# 5V_and_3V3_Outputs.net
KiCad netlist of a schematic drawn in Altium Designer
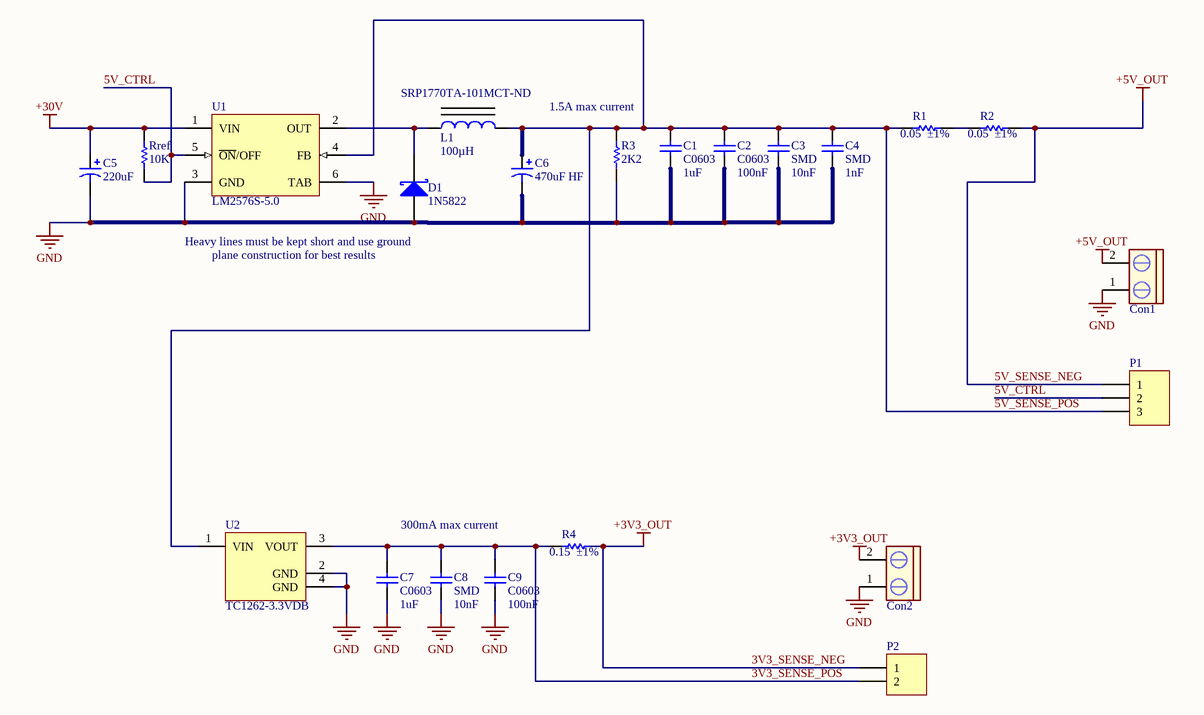
[diagram p0: 5V and 3V3 Outputs.SchDoc]

(export (version "E")
  (design (tool "Eeschema 10.0.6"))
  (components
    (comp (ref "C1")
      (value "C0603")
      (footprint "0603")
      (description "C1608X7R1C105K X7R")
      (fields (field (name "ALTIUM_VALUE") "1uF") (field (name "PUBLISHER") "Altium Limited"))
      (libsource (lib "KEMET Chip Capacitor") (part "C0603"))
    )
    (comp (ref "C2")
      (value "C0603")
      (footprint "0603")
      (description "C1608X7R1C105K X7R")
      (fields (field (name "ALTIUM_VALUE") "100nF") (field (name "PUBLISHER") "Altium Limited"))
      (libsource (lib "KEMET Chip Capacitor") (part "C0603"))
    )
    (comp (ref "C3")
      (value "SMD")
      (footprint "1206")
      (description "Ceramic Chip Capacitor - Standard")
      (fields (field (name "ALTIUM_VALUE") "10nF") (field (name "PUBLISHER") "Altium Limited"))
      (libsource (lib "KEMET Chip Capacitor") (part "C1206"))
    )
    (comp (ref "C4")
      (value "SMD")
      (footprint "1206")
      (description "Ceramic Chip Capacitor - Standard")
      (fields (field (name "ALTIUM_VALUE") "1nF") (field (name "PUBLISHER") "Altium Limited"))
      (libsource (lib "KEMET Chip Capacitor") (part "C1206"))
    )
    (comp (ref "C5")
      (value "220uF")
      (footprint "CAPPR5-10X16")
      (description "Aluminum Electrolytic Capacitor, Radial Style with Long Leads: 220uF, 63V")
      (fields (field (name "PUBLISHER") "Altium Limited"))
      (libsource (lib "Vishay Roederstein Electrolytic Radial-Lead Capacitor") (part "EKA00DD322J00"))
    )
    (comp (ref "C6")
      (value "470uF HF")
      (footprint "CAPPR5-10X20")
      (description "Aluminum Electrolytic Capacitor, Radial Style with Long Leads: 470uF, 25V")
      (fields (field (name "PUBLISHER") "Altium Limited"))
      (libsource (lib "Vishay Roederstein Electrolytic Radial-Lead Capacitor") (part "EKC00DE347E00"))
    )
    (comp (ref "C7")
      (value "C0603")
      (footprint "0603")
      (description "C1608X7R1C105K X7R")
      (fields (field (name "ALTIUM_VALUE") "1uF") (field (name "PUBLISHER") "Altium Limited"))
      (libsource (lib "KEMET Chip Capacitor") (part "C0603"))
    )
    (comp (ref "C8")
      (value "SMD")
      (footprint "1206")
      (description "Ceramic Chip Capacitor - Standard")
      (fields (field (name "ALTIUM_VALUE") "10nF") (field (name "PUBLISHER") "Altium Limited"))
      (libsource (lib "KEMET Chip Capacitor") (part "C1206"))
    )
    (comp (ref "C9")
      (value "C0603")
      (footprint "0603")
      (description "C1608X7R1C105K X7R")
      (fields (field (name "ALTIUM_VALUE") "100nF") (field (name "PUBLISHER") "Altium Limited"))
      (libsource (lib "KEMET Chip Capacitor") (part "C0603"))
    )
    (comp (ref "Con1")
      (value "Salida Buck")
      (footprint "My_CN2")
      (description "Connector blue screw")
      (libsource (lib "Mylib") (part "CON2 pin blue"))
    )
    (comp (ref "Con2")
      (value "Salida Buck")
      (footprint "My_CN2")
      (description "Connector blue screw")
      (libsource (lib "Mylib") (part "CON2 pin blue"))
    )
    (comp (ref "D1")
      (value "1N5822")
      (footprint "Vertical DO-201AD 10.5mm")
      (description "Generic Schottky Diode")
      (libsource (lib "NXT - Diodes") (part "Generic Schottky Diode"))
    )
    (comp (ref "L1")
      (value "Ferrite Inductor")
      (footprint "SRP1770TA Series")
      (fields
        (field (name "MANUFACTURER PART NUMBER") "SRP1770TA-101M")
        (field (name "TOLERANCE") "±20%")
        (field (name "SUPPLIER PART NUMBER") "SRP1770TA-101MCT-ND")
        (field (name "MANUFACTURER") "Bourns Inc.")
        (field (name "INDUCTANCE") "100µH")
      )
      (libsource (lib "NXT - Inductors") (part "Ferrite Inductor"))
    )
    (comp (ref "P1")
      (value "Header 3")
      (footprint "My_1X03")
      (description "Header, 3-Pin")
      (fields (field (name "PUBLISHER") "Altium Limited"))
      (libsource (lib "Mylib") (part "Header 3"))
    )
    (comp (ref "P2")
      (value "Header 2")
      (footprint "My_1X02")
      (description "Header, 2-Pin")
      (fields (field (name "PUBLISHER") "Altium Limited"))
      (libsource (lib "Mylib") (part "Header 2"))
    )
    (comp (ref "R1")
      (value "ERJL1W")
      (footprint "L1W-2512")
      (fields
        (field (name "MANUFACTURER PART NUMBER") "PE2512FKE070R05L")
        (field (name "MANUFACTURER") "Yageo")
        (field (name "RESISTANCE (OHMS)") "0.05")
        (field (name "TOLERANCE") "±1%")
        (field (name "PUBLISHER") "Altium Limited")
      )
      (libsource (lib "Panasonic Resistor") (part "ERJL1W"))
    )
    (comp (ref "R2")
      (value "ERJL1W")
      (footprint "L1W-2512")
      (fields
        (field (name "MANUFACTURER PART NUMBER") "PE2512FKE070R05L")
        (field (name "MANUFACTURER") "Yageo")
        (field (name "RESISTANCE (OHMS)") "0.05")
        (field (name "TOLERANCE") "±1%")
        (field (name "PUBLISHER") "Altium Limited")
      )
      (libsource (lib "Panasonic Resistor") (part "ERJL1W"))
    )
    (comp (ref "R3")
      (value "2K2")
      (footprint "ERA-0603")
      (fields (field (name "PUBLISHER") "Altium Limited"))
      (libsource (lib "Panasonic Resistor") (part "ERA3Y"))
    )
    (comp (ref "R4")
      (value "SMD")
      (footprint "8RB-1206")
      (fields
        (field (name "RESISTANCE (OHMS)") "0.15")
        (field (name "MANUFACTURER PART NUMBER") "KRL1632E-M-R150-F-T5")
        (field (name "TOLERANCE") "±1%")
        (field (name "MANUFACTURER") "Susumu")
      )
      (libsource (lib "Panasonic Resistor") (part "ERJ8BQ"))
    )
    (comp (ref "Rref")
      (value "10K")
      (footprint "ERA-0603")
      (fields (field (name "PUBLISHER") "Altium Limited"))
      (libsource (lib "Panasonic Resistor") (part "ERA3Y"))
    )
    (comp (ref "U1")
      (value "LM2576S-5.0")
      (footprint "TS5B_N")
      (description "SIMPLE SWITCHER® 3A Step-Down Voltage Regulator, 5-pin TO-263")
      (fields (field (name "MANUFACTURER") "National Semiconductor"))
      (libsource (lib "National Semiconductor Switcher") (part "LM2576S-5.0"))
    )
    (comp (ref "U2")
      (value "TC1262-3.3VDB")
      (footprint "SOT-223-DB3_N")
      (description "500mA Fixed Output CMOS LDO, 3-Pin SOT-223, Extended Temperature")
      (fields (field (name "MANUFACTURER") "Microchip"))
      (libsource (lib "Microchip Power Management Line Regulator") (part "TC1262-3.3VDB"))
    )
  )
  (nets
    (net (code "1") (name "+3V3_OUT") (class "Default")
      (node (ref "Con2") (pin "2") (pinfunction "2_2") (pintype "passive"))
      (node (ref "P2") (pin "1") (pinfunction "1_1") (pintype "passive"))
      (node (ref "R4") (pin "2") (pinfunction "2_2") (pintype "passive"))
    )
    (net (code "2") (name "+5V_OUT") (class "Default")
      (node (ref "Con1") (pin "2") (pinfunction "2_2") (pintype "passive"))
      (node (ref "P1") (pin "1") (pinfunction "1_1") (pintype "passive"))
      (node (ref "R2") (pin "2") (pinfunction "2_2") (pintype "passive"))
    )
    (net (code "3") (name "+30V") (class "Default")
      (node (ref "C5") (pin "1") (pinfunction "1_1") (pintype "passive"))
      (node (ref "Rref") (pin "2") (pinfunction "2_2") (pintype "passive"))
      (node (ref "U1") (pin "1") (pinfunction "VIN_1") (pintype "power_in"))
    )
    (net (code "4") (name "/3V3_SENSE_POS") (class "Default")
      (node (ref "C7") (pin "2") (pinfunction "2_2") (pintype "passive"))
      (node (ref "C8") (pin "2") (pinfunction "2_2") (pintype "passive"))
      (node (ref "C9") (pin "2") (pinfunction "2_2") (pintype "passive"))
      (node (ref "P2") (pin "2") (pinfunction "2_2") (pintype "passive"))
      (node (ref "R4") (pin "1") (pinfunction "1_1") (pintype "passive"))
      (node (ref "U2") (pin "3") (pinfunction "VOUT_3") (pintype "power_in"))
    )
    (net (code "5") (name "/5V_CTRL") (class "Default")
      (node (ref "P1") (pin "2") (pinfunction "2_2") (pintype "passive"))
      (node (ref "Rref") (pin "1") (pinfunction "1_1") (pintype "passive"))
      (node (ref "U1") (pin "5") (pinfunction "~{ON}/OFF_5") (pintype "input"))
    )
    (net (code "6") (name "/5V_SENSE_POS") (class "Default")
      (node (ref "C1") (pin "2") (pinfunction "2_2") (pintype "passive"))
      (node (ref "C2") (pin "2") (pinfunction "2_2") (pintype "passive"))
      (node (ref "C3") (pin "2") (pinfunction "2_2") (pintype "passive"))
      (node (ref "C4") (pin "2") (pinfunction "2_2") (pintype "passive"))
      (node (ref "C6") (pin "1") (pinfunction "1_1") (pintype "passive"))
      (node (ref "L1") (pin "2") (pinfunction "2_2") (pintype "passive"))
      (node (ref "P1") (pin "3") (pinfunction "3_3") (pintype "passive"))
      (node (ref "R1") (pin "1") (pinfunction "1_1") (pintype "passive"))
      (node (ref "R3") (pin "2") (pinfunction "2_2") (pintype "passive"))
      (node (ref "U1") (pin "4") (pinfunction "FB_4") (pintype "input"))
      (node (ref "U2") (pin "1") (pinfunction "VIN_1") (pintype "power_in"))
    )
    (net (code "7") (name "GND") (class "Default")
      (node (ref "C1") (pin "1") (pinfunction "1_1") (pintype "passive"))
      (node (ref "C2") (pin "1") (pinfunction "1_1") (pintype "passive"))
      (node (ref "C3") (pin "1") (pinfunction "1_1") (pintype "passive"))
      (node (ref "C4") (pin "1") (pinfunction "1_1") (pintype "passive"))
      (node (ref "C5") (pin "2") (pinfunction "2_2") (pintype "passive"))
      (node (ref "C6") (pin "2") (pinfunction "2_2") (pintype "passive"))
      (node (ref "C7") (pin "1") (pinfunction "1_1") (pintype "passive"))
      (node (ref "C8") (pin "1") (pinfunction "1_1") (pintype "passive"))
      (node (ref "C9") (pin "1") (pinfunction "1_1") (pintype "passive"))
      (node (ref "Con1") (pin "1") (pinfunction "1_1") (pintype "passive"))
      (node (ref "Con2") (pin "1") (pinfunction "1_1") (pintype "passive"))
      (node (ref "D1") (pin "1") (pinfunction "A_1") (pintype "passive"))
      (node (ref "R3") (pin "1") (pinfunction "1_1") (pintype "passive"))
      (node (ref "U1") (pin "3") (pinfunction "GND_3") (pintype "power_in"))
      (node (ref "U1") (pin "6") (pinfunction "TAB_6") (pintype "power_in"))
      (node (ref "U2") (pin "2") (pinfunction "GND_2") (pintype "power_in"))
      (node (ref "U2") (pin "4") (pinfunction "GND_4") (pintype "power_in"))
    )
    (net (code "8") (name "Net-(D1-K)") (class "Default")
      (node (ref "D1") (pin "2") (pinfunction "K_2") (pintype "passive"))
      (node (ref "L1") (pin "1") (pinfunction "1_1") (pintype "passive"))
      (node (ref "U1") (pin "2") (pinfunction "OUT_2") (pintype "power_in"))
    )
    (net (code "9") (name "Net-(R1-Pad2)") (class "Default")
      (node (ref "R1") (pin "2") (pinfunction "2_2") (pintype "passive"))
      (node (ref "R2") (pin "1") (pinfunction "1_1") (pintype "passive"))
    )
  )
)
